# amplificador_stereo_v2.net
KiCad netlist of a schematic drawn in EAGLE
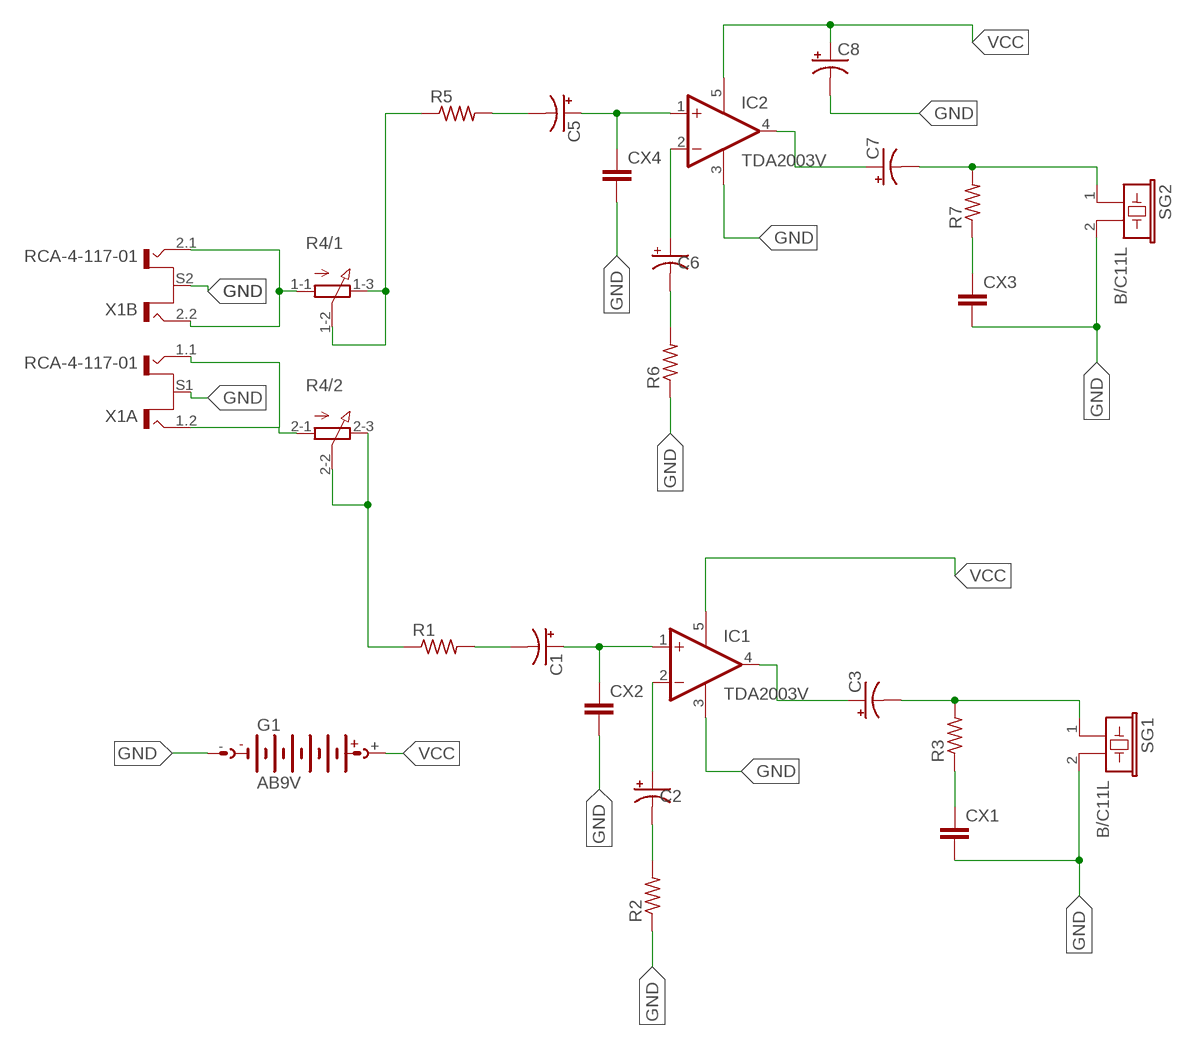
[diagram p0: schematic, sheet 1]

(export (version "E")
  (design (tool "Eeschema 10.0.6"))
  (components
    (comp (ref "C1")
      (value "CPOL-USB45181B")
      (footprint "eagle-import:B45181B")
      (libsource (lib "eagle-import") (part "CPOL-USB45181B"))
    )
    (comp (ref "C2")
      (value "CPOL-USB45181B")
      (footprint "eagle-import:B45181B")
      (libsource (lib "eagle-import") (part "CPOL-USB45181B"))
    )
    (comp (ref "C3")
      (value "CPOL-USB45181B")
      (footprint "eagle-import:B45181B")
      (libsource (lib "eagle-import") (part "CPOL-USB45181B"))
    )
    (comp (ref "C5")
      (value "CPOL-USB45181B")
      (footprint "eagle-import:B45181B")
      (libsource (lib "eagle-import") (part "CPOL-USB45181B"))
    )
    (comp (ref "C6")
      (value "CPOL-USB45181B")
      (footprint "eagle-import:B45181B")
      (libsource (lib "eagle-import") (part "CPOL-USB45181B"))
    )
    (comp (ref "C7")
      (value "CPOL-USB45181B")
      (footprint "eagle-import:B45181B")
      (libsource (lib "eagle-import") (part "CPOL-USB45181B"))
    )
    (comp (ref "C8")
      (value "CPOL-USB45181B")
      (footprint "eagle-import:B45181B")
      (libsource (lib "eagle-import") (part "CPOL-USB45181B"))
    )
    (comp (ref "CX1")
      (value "C-EU050-045X075")
      (footprint "eagle-import:C050-045X075")
      (libsource (lib "eagle-import") (part "C-EU050-045X075"))
    )
    (comp (ref "CX2")
      (value "C-EU050-045X075")
      (footprint "eagle-import:C050-045X075")
      (libsource (lib "eagle-import") (part "C-EU050-045X075"))
    )
    (comp (ref "CX3")
      (value "C-EU050-035X075")
      (footprint "eagle-import:C050-035X075")
      (libsource (lib "eagle-import") (part "C-EU050-035X075"))
    )
    (comp (ref "CX4")
      (value "C-EU050-045X075")
      (footprint "eagle-import:C050-045X075")
      (libsource (lib "eagle-import") (part "C-EU050-045X075"))
    )
    (comp (ref "G1")
      (value "AB9V")
      (footprint "eagle-import:AB9V")
      (libsource (lib "eagle-import") (part "AB9V"))
    )
    (comp (ref "IC1")
      (value "TDA2003V")
      (footprint "eagle-import:CB360")
      (libsource (lib "eagle-import") (part "TDA2003V"))
    )
    (comp (ref "IC2")
      (value "TDA2003V")
      (footprint "eagle-import:CB360")
      (libsource (lib "eagle-import") (part "TDA2003V"))
    )
    (comp (ref "R1")
      (value "R-US_0204/7")
      (footprint "eagle-import:0204_7")
      (libsource (lib "eagle-import") (part "R-US_0204/7"))
    )
    (comp (ref "R2")
      (value "R-US_0204/7")
      (footprint "eagle-import:0204_7")
      (libsource (lib "eagle-import") (part "R-US_0204/7"))
    )
    (comp (ref "R3")
      (value "R-US_0204/7")
      (footprint "eagle-import:0204_7")
      (libsource (lib "eagle-import") (part "R-US_0204/7"))
    )
    (comp (ref "R4")
      (value "3RP/1610G")
      (footprint "eagle-import:3RP_1610G")
      (libsource (lib "eagle-import") (part "3RP/1610G"))
    )
    (comp (ref "R5")
      (value "R-US_0204/7")
      (footprint "eagle-import:0204_7")
      (libsource (lib "eagle-import") (part "R-US_0204/7"))
    )
    (comp (ref "R6")
      (value "R-US_0204/7")
      (footprint "eagle-import:0204_7")
      (libsource (lib "eagle-import") (part "R-US_0204/7"))
    )
    (comp (ref "R7")
      (value "R-US_0204/7")
      (footprint "eagle-import:0204_7")
      (libsource (lib "eagle-import") (part "R-US_0204/7"))
    )
    (comp (ref "SG1")
      (value "B/C11L")
      (footprint "eagle-import:B_C11L")
      (libsource (lib "eagle-import") (part "B/C11L"))
    )
    (comp (ref "SG2")
      (value "B/C11L")
      (footprint "eagle-import:B_C11L")
      (libsource (lib "eagle-import") (part "B/C11L"))
    )
    (comp (ref "X1")
      (value "RCA-4-117-01")
      (footprint "eagle-import:RCA-4-117-01")
      (libsource (lib "eagle-import") (part "RCA-4-117-01"))
    )
  )
  (nets
    (net (code "1") (name "GND") (class "Default")
      (node (ref "C8") (pin "-") (pinfunction "-_-") (pintype "passive"))
      (node (ref "CX1") (pin "2") (pinfunction "2_2") (pintype "passive"))
      (node (ref "CX2") (pin "2") (pinfunction "2_2") (pintype "passive"))
      (node (ref "CX3") (pin "2") (pinfunction "2_2") (pintype "passive"))
      (node (ref "CX4") (pin "2") (pinfunction "2_2") (pintype "passive"))
      (node (ref "G1") (pin "-") (pinfunction "-_-") (pintype "passive"))
      (node (ref "IC1") (pin "3") (pinfunction "GND_3") (pintype "power_in"))
      (node (ref "IC2") (pin "3") (pinfunction "GND_3") (pintype "power_in"))
      (node (ref "R2") (pin "1") (pinfunction "1_1") (pintype "passive"))
      (node (ref "R6") (pin "1") (pinfunction "1_1") (pintype "passive"))
      (node (ref "SG1") (pin "2") (pinfunction "2_2") (pintype "passive"))
      (node (ref "SG2") (pin "2") (pinfunction "2_2") (pintype "passive"))
      (node (ref "X1") (pin "S1") (pinfunction "S_S1") (pintype "passive"))
      (node (ref "X1") (pin "S2") (pinfunction "S_S2") (pintype "passive"))
    )
    (net (code "2") (name "Net-(C1-Pad-)") (class "Default")
      (node (ref "C1") (pin "-") (pinfunction "-_-") (pintype "passive"))
      (node (ref "R1") (pin "2") (pinfunction "2_2") (pintype "passive"))
    )
    (net (code "3") (name "Net-(C2-Pad-)") (class "Default")
      (node (ref "C2") (pin "-") (pinfunction "-_-") (pintype "passive"))
      (node (ref "R2") (pin "2") (pinfunction "2_2") (pintype "passive"))
    )
    (net (code "4") (name "Net-(C3-Pad-)") (class "Default")
      (node (ref "C3") (pin "-") (pinfunction "-_-") (pintype "passive"))
      (node (ref "R3") (pin "2") (pinfunction "2_2") (pintype "passive"))
      (node (ref "SG1") (pin "1") (pinfunction "1_1") (pintype "passive"))
    )
    (net (code "5") (name "Net-(C5-Pad-)") (class "Default")
      (node (ref "C5") (pin "-") (pinfunction "-_-") (pintype "passive"))
      (node (ref "R5") (pin "2") (pinfunction "2_2") (pintype "passive"))
    )
    (net (code "6") (name "Net-(C6-Pad-)") (class "Default")
      (node (ref "C6") (pin "-") (pinfunction "-_-") (pintype "passive"))
      (node (ref "R6") (pin "2") (pinfunction "2_2") (pintype "passive"))
    )
    (net (code "7") (name "Net-(C7-Pad-)") (class "Default")
      (node (ref "C7") (pin "-") (pinfunction "-_-") (pintype "passive"))
      (node (ref "R7") (pin "2") (pinfunction "2_2") (pintype "passive"))
      (node (ref "SG2") (pin "1") (pinfunction "1_1") (pintype "passive"))
    )
    (net (code "8") (name "Net-(CX1-Pad1)") (class "Default")
      (node (ref "CX1") (pin "1") (pinfunction "1_1") (pintype "passive"))
      (node (ref "R3") (pin "1") (pinfunction "1_1") (pintype "passive"))
    )
    (net (code "9") (name "Net-(CX3-Pad1)") (class "Default")
      (node (ref "CX3") (pin "1") (pinfunction "1_1") (pintype "passive"))
      (node (ref "R7") (pin "1") (pinfunction "1_1") (pintype "passive"))
    )
    (net (code "10") (name "Net-(IC1-+IN)") (class "Default")
      (node (ref "C1") (pin "+") (pinfunction "+_+") (pintype "passive"))
      (node (ref "CX2") (pin "1") (pinfunction "1_1") (pintype "passive"))
      (node (ref "IC1") (pin "1") (pinfunction "+IN_1") (pintype "input"))
    )
    (net (code "11") (name "Net-(IC1--IN)") (class "Default")
      (node (ref "C2") (pin "+") (pinfunction "+_+") (pintype "passive"))
      (node (ref "IC1") (pin "2") (pinfunction "-IN_2") (pintype "input"))
    )
    (net (code "12") (name "Net-(IC1-OUT)") (class "Default")
      (node (ref "C3") (pin "+") (pinfunction "+_+") (pintype "passive"))
      (node (ref "IC1") (pin "4") (pinfunction "OUT_4") (pintype "output"))
    )
    (net (code "13") (name "Net-(IC2-+IN)") (class "Default")
      (node (ref "C5") (pin "+") (pinfunction "+_+") (pintype "passive"))
      (node (ref "CX4") (pin "1") (pinfunction "1_1") (pintype "passive"))
      (node (ref "IC2") (pin "1") (pinfunction "+IN_1") (pintype "input"))
    )
    (net (code "14") (name "Net-(IC2--IN)") (class "Default")
      (node (ref "C6") (pin "+") (pinfunction "+_+") (pintype "passive"))
      (node (ref "IC2") (pin "2") (pinfunction "-IN_2") (pintype "input"))
    )
    (net (code "15") (name "Net-(IC2-OUT)") (class "Default")
      (node (ref "C7") (pin "+") (pinfunction "+_+") (pintype "passive"))
      (node (ref "IC2") (pin "4") (pinfunction "OUT_4") (pintype "output"))
    )
    (net (code "16") (name "Net-(R4A-A)") (class "Default")
      (node (ref "R4") (pin "1-1") (pinfunction "A_1-1") (pintype "passive"))
      (node (ref "X1") (pin "2.1") (pinfunction "T1_2.1") (pintype "passive"))
      (node (ref "X1") (pin "2.2") (pinfunction "T2_2.2") (pintype "passive"))
    )
    (net (code "17") (name "Net-(R4A-E)") (class "Default")
      (node (ref "R4") (pin "1-2") (pinfunction "S_1-2") (pintype "passive"))
      (node (ref "R4") (pin "1-3") (pinfunction "E_1-3") (pintype "passive"))
      (node (ref "R5") (pin "1") (pinfunction "1_1") (pintype "passive"))
    )
    (net (code "18") (name "Net-(R4B-A)") (class "Default")
      (node (ref "R4") (pin "2-1") (pinfunction "A_2-1") (pintype "passive"))
      (node (ref "X1") (pin "1.1") (pinfunction "T1_1.1") (pintype "passive"))
      (node (ref "X1") (pin "1.2") (pinfunction "T2_1.2") (pintype "passive"))
    )
    (net (code "19") (name "Net-(R4B-E)") (class "Default")
      (node (ref "R1") (pin "1") (pinfunction "1_1") (pintype "passive"))
      (node (ref "R4") (pin "2-2") (pinfunction "S_2-2") (pintype "passive"))
      (node (ref "R4") (pin "2-3") (pinfunction "E_2-3") (pintype "passive"))
    )
    (net (code "20") (name "VCC") (class "Default")
      (node (ref "C8") (pin "+") (pinfunction "+_+") (pintype "passive"))
      (node (ref "G1") (pin "+") (pinfunction "+_+") (pintype "passive"))
      (node (ref "IC1") (pin "5") (pinfunction "V+_5") (pintype "power_in"))
      (node (ref "IC2") (pin "5") (pinfunction "V+_5") (pintype "power_in"))
    )
  )
)
